# 2_Bypass_Balance.net
KiCad netlist of a schematic drawn in Altium Designer
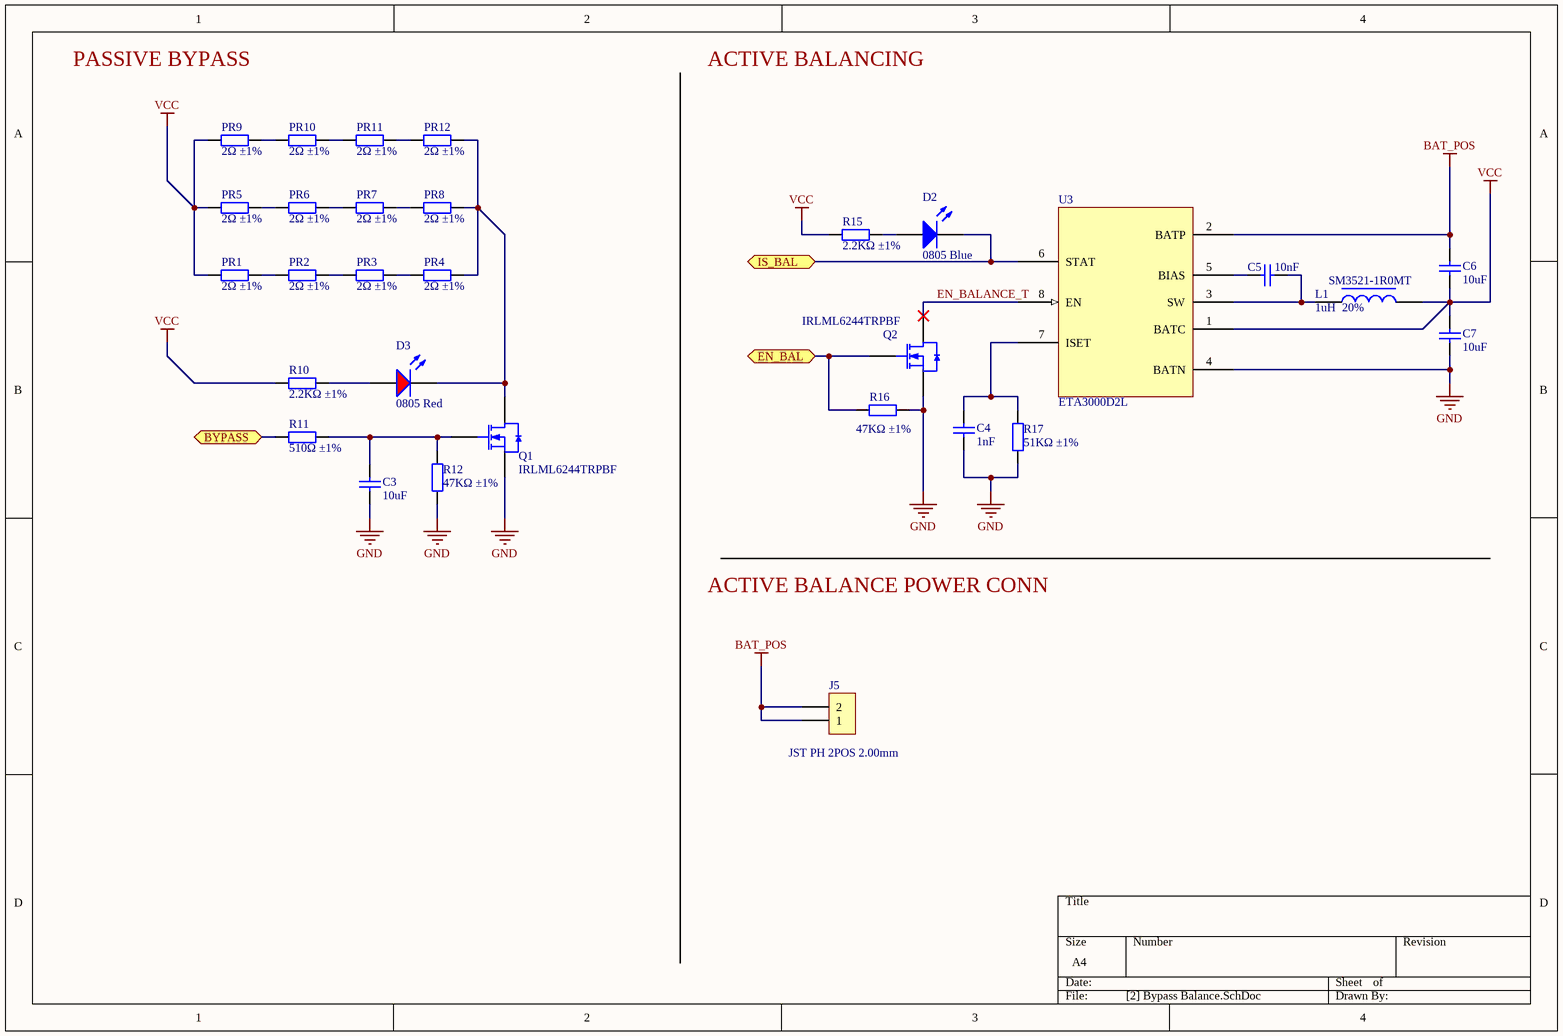
[diagram p0: [2] Bypass Balance.SchDoc]

(export (version "E")
  (design (tool "Eeschema 10.0.6"))
  (components
    (comp (ref "C3")
      (value "10uF")
      (footprint "0805_C")
      (description "Chip capacitors")
      (fields
        (field (name "MANUFACTURER") "Samsung Electro-Mechanics")
        (field (name "PARTNUMBER") "CL21A106KAYNNNE")
      )
      (libsource (lib "Miscellaneous Devices LC") (part "0805 10uF (106) 10% 25V"))
    )
    (comp (ref "C4")
      (value "1nF")
      (footprint "0805_C")
      (description "Chip capacitors")
      (fields
        (field (name "MANUFACTURER") "Samsung Electro-Mechanics")
        (field (name "PARTNUMBER") "CL21B102KBCNNNC")
      )
      (libsource (lib "Cap") (part "0805 1nF (102) 10% 50V"))
    )
    (comp (ref "C5")
      (value "10nF")
      (footprint "0805_C")
      (description "Chip capacitors")
      (fields
        (field (name "MANUFACTURER") "Samsung Electro-Mechanics")
        (field (name "PARTNUMBER") "CL21B103KBANNNC")
      )
      (libsource (lib "Miscellaneous Devices LC") (part "0805 10nF (103) 10% 50V"))
    )
    (comp (ref "C6")
      (value "10uF")
      (footprint "0805_C")
      (description "Chip capacitors")
      (fields
        (field (name "MANUFACTURER") "Samsung Electro-Mechanics")
        (field (name "PARTNUMBER") "CL21A106KAYNNNE")
      )
      (libsource (lib "Miscellaneous Devices LC") (part "0805 10uF (106) 10% 25V"))
    )
    (comp (ref "C7")
      (value "10uF")
      (footprint "0805_C")
      (description "Chip capacitors")
      (fields
        (field (name "MANUFACTURER") "Samsung Electro-Mechanics")
        (field (name "PARTNUMBER") "CL21A106KAYNNNE")
      )
      (libsource (lib "Miscellaneous Devices LC") (part "0805 10uF (106) 10% 25V"))
    )
    (comp (ref "D2")
      (value "0805 Blue")
      (footprint "0805_LED_S1")
      (description "LED")
      (libsource (lib "LED") (part "0805 LED Blue"))
    )
    (comp (ref "D3")
      (value "0805 Red")
      (footprint "0805_LED_S1")
      (description "LED")
      (fields
        (field (name "PARTNUMBER") "FC-2012HRK-620D")
        (field (name "MANUFACTURER") "Foshan NationStar Optoelectronics")
      )
      (libsource (lib "LED") (part "0805 LED Red"))
    )
    (comp (ref "J5")
      (value "JST PH 2POS 2.00mm")
      (footprint "JST_PH_S2B")
      (description "JST-PH Conn")
      (fields
        (field (name "MANUFACTURER") "JST Sales America")
        (field (name "PARTNUMBER") "S2B-PH-K-S(LF)(SN)")
      )
      (libsource (lib "BMS_SchLib") (part "JST_PH_2POS"))
    )
    (comp (ref "L1")
      (value "SM3521-1R0MT")
      (footprint "3521_L")
      (description "Power Inductor")
      (fields
        (field (name "MANUFACTURER") "Shun Xiang Nuo Elec")
        (field (name "TOLERANCE") "20%")
        (field (name "INDUCTANCE") "1uH")
      )
      (libsource (lib "BMS_SchLib") (part "3521 1uH 20%"))
    )
    (comp (ref "PR1")
      (value "2Ω ±1%")
      (footprint "2512_R")
      (description "Chip resistor")
      (fields (field (name "MANUFACTURER") "Uniroyal Elec") (field (name "PARTNUMBER") "25121WF200KT4E"))
      (libsource (lib "BMS_SchLib") (part "2512 2R (2R00) 1%"))
    )
    (comp (ref "PR2")
      (value "2Ω ±1%")
      (footprint "2512_R")
      (description "Chip resistor")
      (fields (field (name "MANUFACTURER") "Uniroyal Elec") (field (name "PARTNUMBER") "25121WF200KT4E"))
      (libsource (lib "BMS_SchLib") (part "2512 2R (2R00) 1%"))
    )
    (comp (ref "PR3")
      (value "2Ω ±1%")
      (footprint "2512_R")
      (description "Chip resistor")
      (fields (field (name "MANUFACTURER") "Uniroyal Elec") (field (name "PARTNUMBER") "25121WF200KT4E"))
      (libsource (lib "BMS_SchLib") (part "2512 2R (2R00) 1%"))
    )
    (comp (ref "PR4")
      (value "2Ω ±1%")
      (footprint "2512_R")
      (description "Chip resistor")
      (fields (field (name "MANUFACTURER") "Uniroyal Elec") (field (name "PARTNUMBER") "25121WF200KT4E"))
      (libsource (lib "BMS_SchLib") (part "2512 2R (2R00) 1%"))
    )
    (comp (ref "PR5")
      (value "2Ω ±1%")
      (footprint "2512_R")
      (description "Chip resistor")
      (fields (field (name "MANUFACTURER") "Uniroyal Elec") (field (name "PARTNUMBER") "25121WF200KT4E"))
      (libsource (lib "BMS_SchLib") (part "2512 2R (2R00) 1%"))
    )
    (comp (ref "PR6")
      (value "2Ω ±1%")
      (footprint "2512_R")
      (description "Chip resistor")
      (fields (field (name "MANUFACTURER") "Uniroyal Elec") (field (name "PARTNUMBER") "25121WF200KT4E"))
      (libsource (lib "BMS_SchLib") (part "2512 2R (2R00) 1%"))
    )
    (comp (ref "PR7")
      (value "2Ω ±1%")
      (footprint "2512_R")
      (description "Chip resistor")
      (fields (field (name "MANUFACTURER") "Uniroyal Elec") (field (name "PARTNUMBER") "25121WF200KT4E"))
      (libsource (lib "BMS_SchLib") (part "2512 2R (2R00) 1%"))
    )
    (comp (ref "PR8")
      (value "2Ω ±1%")
      (footprint "2512_R")
      (description "Chip resistor")
      (fields (field (name "MANUFACTURER") "Uniroyal Elec") (field (name "PARTNUMBER") "25121WF200KT4E"))
      (libsource (lib "BMS_SchLib") (part "2512 2R (2R00) 1%"))
    )
    (comp (ref "PR9")
      (value "2Ω ±1%")
      (footprint "2512_R")
      (description "Chip resistor")
      (fields (field (name "MANUFACTURER") "Uniroyal Elec") (field (name "PARTNUMBER") "25121WF200KT4E"))
      (libsource (lib "BMS_SchLib") (part "2512 2R (2R00) 1%"))
    )
    (comp (ref "PR10")
      (value "2Ω ±1%")
      (footprint "2512_R")
      (description "Chip resistor")
      (fields (field (name "MANUFACTURER") "Uniroyal Elec") (field (name "PARTNUMBER") "25121WF200KT4E"))
      (libsource (lib "BMS_SchLib") (part "2512 2R (2R00) 1%"))
    )
    (comp (ref "PR11")
      (value "2Ω ±1%")
      (footprint "2512_R")
      (description "Chip resistor")
      (fields (field (name "MANUFACTURER") "Uniroyal Elec") (field (name "PARTNUMBER") "25121WF200KT4E"))
      (libsource (lib "BMS_SchLib") (part "2512 2R (2R00) 1%"))
    )
    (comp (ref "PR12")
      (value "2Ω ±1%")
      (footprint "2512_R")
      (description "Chip resistor")
      (fields (field (name "MANUFACTURER") "Uniroyal Elec") (field (name "PARTNUMBER") "25121WF200KT4E"))
      (libsource (lib "BMS_SchLib") (part "2512 2R (2R00) 1%"))
    )
    (comp (ref "Q1")
      (value "IRLML6244TRPBF")
      (footprint "SOT-23(SOT-23-3)")
      (description "MOSFET-N")
      (fields (field (name "MANUFACTURER") "Infineon Technologies"))
      (libsource (lib "BMS_SchLib") (part "IRLML6244"))
    )
    (comp (ref "Q2")
      (value "IRLML6244TRPBF")
      (footprint "SOT-23(SOT-23-3)")
      (description "MOSFET-N")
      (fields (field (name "MANUFACTURER") "Infineon Technologies"))
      (libsource (lib "BMS_SchLib") (part "IRLML6244"))
    )
    (comp (ref "R10")
      (value "2.2KΩ ±1%")
      (footprint "0805_R")
      (description "Chip resistor")
      (fields (field (name "MANUFACTURER") "Uniroyal Elec") (field (name "PARTNUMBER") "0805W8F2201T5E"))
      (libsource (lib "RES") (part "0805 2.2K (2201) 1%"))
    )
    (comp (ref "R11")
      (value "510Ω ±1%")
      (footprint "0805_R")
      (description "Chip resistor")
      (fields (field (name "MANUFACTURER") "Uniroyal Elec") (field (name "PARTNUMBER") "0805W8F5100T5E"))
      (libsource (lib "RES") (part "0805 510R (5100) 1%"))
    )
    (comp (ref "R12")
      (value "47KΩ ±1%")
      (footprint "0805_R")
      (description "Chip resistor")
      (fields (field (name "MANUFACTURER") "Uniroyal Elec") (field (name "PARTNUMBER") "0805W8F4702T5E"))
      (libsource (lib "") (part "0805 47K (4702) 1%_1"))
    )
    (comp (ref "R15")
      (value "2.2KΩ ±1%")
      (footprint "0805_R")
      (description "Chip resistor")
      (fields (field (name "MANUFACTURER") "Uniroyal Elec") (field (name "PARTNUMBER") "0805W8F2201T5E"))
      (libsource (lib "") (part "0805 2.2K (2201) 1%_1"))
    )
    (comp (ref "R16")
      (value "47KΩ ±1%")
      (footprint "0805_R")
      (description "Chip resistor")
      (fields (field (name "MANUFACTURER") "Uniroyal Elec") (field (name "PARTNUMBER") "0805W8F4702T5E"))
      (libsource (lib "RES") (part "0805 47K (4702) 1%"))
    )
    (comp (ref "R17")
      (value "51KΩ ±1%")
      (footprint "0805_R")
      (description "Chip resistor")
      (fields (field (name "MANUFACTURER") "Uniroyal Elec") (field (name "PARTNUMBER") "0805W8F5102T5E"))
      (libsource (lib "RES") (part "0805 51K (5102) 1%"))
    )
    (comp (ref "U3")
      (value "ETA3000D2L")
      (footprint "DFN2x2-8L")
      (description "Inductive Cell Balancer IC")
      (fields (field (name "MANUFACTURER") "ETA Solutions"))
      (libsource (lib "BMS_SchLib") (part "ETA3000"))
    )
  )
  (nets
    (net (code "1") (name "/BYPASS") (class "Default")
      (node (ref "R11") (pin "1") (pinfunction "1_1") (pintype "passive"))
    )
    (net (code "2") (name "/EN_BAL") (class "Default")
      (node (ref "Q2") (pin "1") (pinfunction "G_1") (pintype "passive"))
      (node (ref "R16") (pin "2") (pinfunction "2_2") (pintype "passive"))
    )
    (net (code "3") (name "/EN_BALANCE_T") (class "Default")
      (node (ref "Q2") (pin "3") (pinfunction "D_3") (pintype "passive"))
      (node (ref "U3") (pin "8") (pinfunction "EN_8") (pintype "input"))
    )
    (net (code "4") (name "/IS_BAL") (class "Default")
      (node (ref "D2") (pin "K") (pinfunction "K_K") (pintype "passive"))
      (node (ref "U3") (pin "6") (pinfunction "STAT_6") (pintype "open_collector"))
    )
    (net (code "5") (name "BAT_POS") (class "Default")
      (node (ref "C6") (pin "2") (pinfunction "2_2") (pintype "passive"))
      (node (ref "J5") (pin "1") (pinfunction "1_1") (pintype "passive"))
      (node (ref "J5") (pin "2") (pinfunction "2_2") (pintype "passive"))
      (node (ref "U3") (pin "2") (pinfunction "BATP_2") (pintype "power_in"))
    )
    (net (code "6") (name "GND") (class "Default")
      (node (ref "C3") (pin "1") (pinfunction "1_1") (pintype "passive"))
      (node (ref "C4") (pin "1") (pinfunction "1_1") (pintype "passive"))
      (node (ref "C7") (pin "1") (pinfunction "1_1") (pintype "passive"))
      (node (ref "Q1") (pin "2") (pinfunction "S_2") (pintype "passive"))
      (node (ref "Q2") (pin "2") (pinfunction "S_2") (pintype "passive"))
      (node (ref "R12") (pin "1") (pinfunction "1_1") (pintype "passive"))
      (node (ref "R16") (pin "1") (pinfunction "1_1") (pintype "passive"))
      (node (ref "R17") (pin "1") (pinfunction "1_1") (pintype "passive"))
      (node (ref "U3") (pin "4") (pinfunction "BATN_4") (pintype "power_in"))
    )
    (net (code "7") (name "Net-(D2-PadA)") (class "Default")
      (node (ref "D2") (pin "A") (pinfunction "A_A") (pintype "passive"))
      (node (ref "R15") (pin "2") (pinfunction "2_2") (pintype "passive"))
    )
    (net (code "8") (name "Net-(D3-PadA)") (class "Default")
      (node (ref "D3") (pin "A") (pinfunction "A_A") (pintype "passive"))
      (node (ref "R10") (pin "1") (pinfunction "1_1") (pintype "passive"))
    )
    (net (code "9") (name "Net-(PR1-Pad1)") (class "Default")
      (node (ref "PR1") (pin "1") (pinfunction "1_1") (pintype "passive"))
      (node (ref "PR2") (pin "2") (pinfunction "2_2") (pintype "passive"))
    )
    (net (code "10") (name "Net-(PR2-Pad1)") (class "Default")
      (node (ref "PR2") (pin "1") (pinfunction "1_1") (pintype "passive"))
      (node (ref "PR3") (pin "2") (pinfunction "2_2") (pintype "passive"))
    )
    (net (code "11") (name "Net-(PR3-Pad1)") (class "Default")
      (node (ref "PR3") (pin "1") (pinfunction "1_1") (pintype "passive"))
      (node (ref "PR4") (pin "2") (pinfunction "2_2") (pintype "passive"))
    )
    (net (code "12") (name "Net-(PR5-Pad1)") (class "Default")
      (node (ref "PR5") (pin "1") (pinfunction "1_1") (pintype "passive"))
      (node (ref "PR6") (pin "2") (pinfunction "2_2") (pintype "passive"))
    )
    (net (code "13") (name "Net-(PR6-Pad1)") (class "Default")
      (node (ref "PR6") (pin "1") (pinfunction "1_1") (pintype "passive"))
      (node (ref "PR7") (pin "2") (pinfunction "2_2") (pintype "passive"))
    )
    (net (code "14") (name "Net-(PR7-Pad1)") (class "Default")
      (node (ref "PR7") (pin "1") (pinfunction "1_1") (pintype "passive"))
      (node (ref "PR8") (pin "2") (pinfunction "2_2") (pintype "passive"))
    )
    (net (code "15") (name "Net-(PR10-Pad1)") (class "Default")
      (node (ref "PR10") (pin "1") (pinfunction "1_1") (pintype "passive"))
      (node (ref "PR11") (pin "2") (pinfunction "2_2") (pintype "passive"))
    )
    (net (code "16") (name "Net-(PR10-Pad2)") (class "Default")
      (node (ref "PR10") (pin "2") (pinfunction "2_2") (pintype "passive"))
      (node (ref "PR9") (pin "1") (pinfunction "1_1") (pintype "passive"))
    )
    (net (code "17") (name "Net-(PR11-Pad1)") (class "Default")
      (node (ref "PR11") (pin "1") (pinfunction "1_1") (pintype "passive"))
      (node (ref "PR12") (pin "2") (pinfunction "2_2") (pintype "passive"))
    )
    (net (code "18") (name "Net-(Q1-D)") (class "Default")
      (node (ref "D3") (pin "K") (pinfunction "K_K") (pintype "passive"))
      (node (ref "PR12") (pin "1") (pinfunction "1_1") (pintype "passive"))
      (node (ref "PR4") (pin "1") (pinfunction "1_1") (pintype "passive"))
      (node (ref "PR8") (pin "1") (pinfunction "1_1") (pintype "passive"))
      (node (ref "Q1") (pin "3") (pinfunction "D_3") (pintype "passive"))
    )
    (net (code "19") (name "Net-(Q1-G)") (class "Default")
      (node (ref "C3") (pin "2") (pinfunction "2_2") (pintype "passive"))
      (node (ref "Q1") (pin "1") (pinfunction "G_1") (pintype "passive"))
      (node (ref "R11") (pin "2") (pinfunction "2_2") (pintype "passive"))
      (node (ref "R12") (pin "2") (pinfunction "2_2") (pintype "passive"))
    )
    (net (code "20") (name "Net-(U3-BIAS)") (class "Default")
      (node (ref "C5") (pin "2") (pinfunction "2_2") (pintype "passive"))
      (node (ref "U3") (pin "5") (pinfunction "BIAS_5") (pintype "passive"))
    )
    (net (code "21") (name "Net-(U3-ISET)") (class "Default")
      (node (ref "C4") (pin "2") (pinfunction "2_2") (pintype "passive"))
      (node (ref "R17") (pin "2") (pinfunction "2_2") (pintype "passive"))
      (node (ref "U3") (pin "7") (pinfunction "ISET_7") (pintype "power_in"))
    )
    (net (code "22") (name "Net-(U3-SW)") (class "Default")
      (node (ref "C5") (pin "1") (pinfunction "1_1") (pintype "passive"))
      (node (ref "L1") (pin "1") (pinfunction "1_1") (pintype "passive"))
      (node (ref "U3") (pin "3") (pinfunction "SW_3") (pintype "passive"))
    )
    (net (code "23") (name "VCC") (class "Default")
      (node (ref "C6") (pin "1") (pinfunction "1_1") (pintype "passive"))
      (node (ref "C7") (pin "2") (pinfunction "2_2") (pintype "passive"))
      (node (ref "L1") (pin "2") (pinfunction "2_2") (pintype "passive"))
      (node (ref "PR1") (pin "2") (pinfunction "2_2") (pintype "passive"))
      (node (ref "PR5") (pin "2") (pinfunction "2_2") (pintype "passive"))
      (node (ref "PR9") (pin "2") (pinfunction "2_2") (pintype "passive"))
      (node (ref "R10") (pin "2") (pinfunction "2_2") (pintype "passive"))
      (node (ref "R15") (pin "1") (pinfunction "1_1") (pintype "passive"))
      (node (ref "U3") (pin "1") (pinfunction "BATC_1") (pintype "power_in"))
    )
  )
)
